# Voltage_regulator.net
KiCad netlist of a schematic drawn in Altium Designer
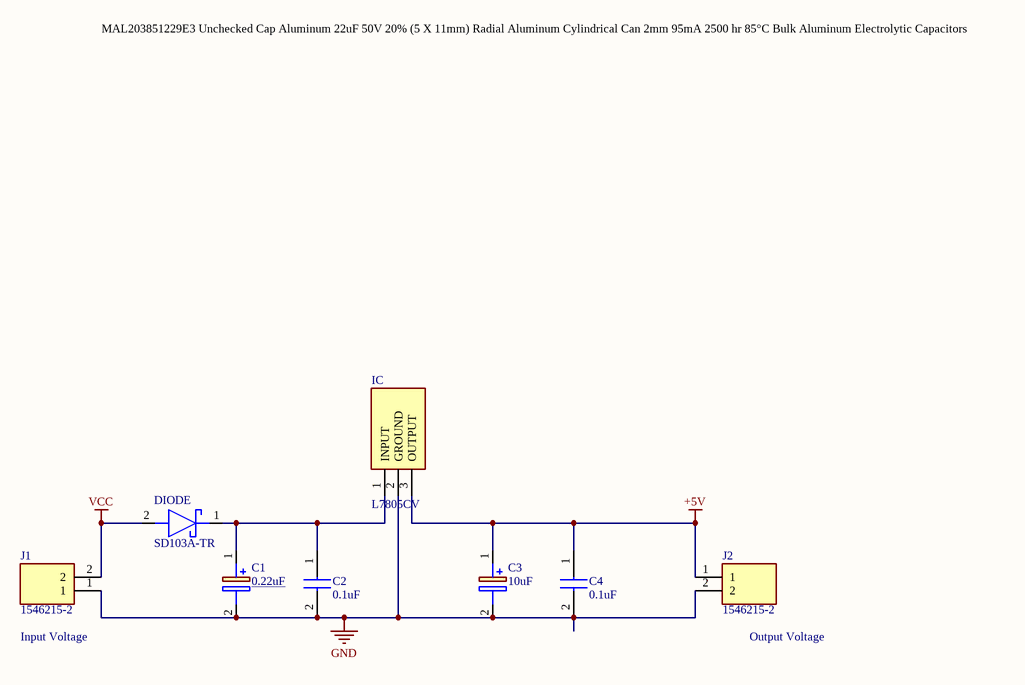
[diagram p0: Voltage_regulator.SchDoc]

(export (version "E")
  (design (tool "Eeschema 10.0.6"))
  (components
    (comp (ref "C1")
      (value "0.22uF")
      (footprint "SamacSys:CAPAE430X600N")
      (description "Capacitor Polarised")
      (fields
        (field (name "MANUFACTURER_PART_NUMBER") "224SML050MD4")
        (field (name "MOUSER PART NUMBER") "598-224SML050MD4")
      )
      (libsource (lib "*") (part "224SML050MD4"))
    )
    (comp (ref "C2")
      (value "0.1uF")
      (footprint "SamacSys:S104Z93Z5VL83L0R")
      (description "Capacitor")
      (fields
        (field (name "MANUFACTURER_PART_NUMBER") "S104Z93Z5VL83L0R")
        (field (name "MOUSER PART NUMBER") "594-S104Z93Z5VL83L0R")
      )
      (libsource (lib "*") (part "S104Z93Z5VL83L0R"))
    )
    (comp (ref "C3")
      (value "10uF")
      (footprint "SamacSys:CAPPRD200W55D500H1250")
      (description "Capacitor Polarised")
      (fields
        (field (name "MANUFACTURER_PART_NUMBER") "EEU-FR1H100")
        (field (name "MOUSER PART NUMBER") "667-EEU-FR1H100")
      )
      (libsource (lib "*") (part "EEU-FR1H100"))
    )
    (comp (ref "C4")
      (value "0.1uF")
      (footprint "SamacSys:S104Z93Z5VL83L0R")
      (description "Capacitor")
      (fields
        (field (name "MANUFACTURER_PART_NUMBER") "S104Z93Z5VL83L0R")
        (field (name "MOUSER PART NUMBER") "594-S104Z93Z5VL83L0R")
      )
      (libsource (lib "*") (part "S104Z93Z5VL83L0R"))
    )
    (comp (ref "DIODE")
      (value "SD103A-TR")
      (footprint "SamacSys:DIOAD950W60L350D150")
      (description "Schottky Diode")
      (fields (field (name "MOUSER PART NUMBER") "625-SD103A"))
      (libsource (lib "*") (part "SD103A-TR"))
    )
    (comp (ref "IC")
      (value "L7805CV")
      (footprint "SamacSys:TO255P460X1020X2008-3P")
      (description "Integrated Circuit")
      (fields (field (name "MOUSER PART NUMBER") "511-L7805CV"))
      (libsource (lib "*") (part "L7805CV"))
    )
    (comp (ref "J1")
      (value "1546215-2")
      (footprint "SamacSys:15462152")
      (description "Connector")
      (fields (field (name "MOUSER PART NUMBER") "571-1546215-2"))
      (libsource (lib "*") (part "1546215-2"))
    )
    (comp (ref "J2")
      (value "1546215-2")
      (footprint "SamacSys:15462152")
      (description "Connector")
      (fields (field (name "MOUSER PART NUMBER") "571-1546215-2"))
      (libsource (lib "") (part "1546215-2_1"))
    )
  )
  (nets
    (net (code "1") (name "+5V") (class "Default")
      (node (ref "C3") (pin "1") (pinfunction "+_1") (pintype "power_in"))
      (node (ref "C4") (pin "1") (pinfunction "1_1") (pintype "passive"))
      (node (ref "IC") (pin "3") (pinfunction "OUTPUT_3") (pintype "passive"))
      (node (ref "J2") (pin "1") (pinfunction "1_1") (pintype "passive"))
    )
    (net (code "2") (name "GND") (class "Default")
      (node (ref "C1") (pin "2") (pinfunction "-_2") (pintype "passive"))
      (node (ref "C2") (pin "2") (pinfunction "2_2") (pintype "passive"))
      (node (ref "C3") (pin "2") (pinfunction "-_2") (pintype "power_in"))
      (node (ref "C4") (pin "2") (pinfunction "2_2") (pintype "passive"))
      (node (ref "IC") (pin "2") (pinfunction "GROUND_2") (pintype "passive"))
      (node (ref "J1") (pin "1") (pinfunction "1_1") (pintype "passive"))
      (node (ref "J2") (pin "2") (pinfunction "2_2") (pintype "passive"))
    )
    (net (code "3") (name "Net-(C1-+)") (class "Default")
      (node (ref "C1") (pin "1") (pinfunction "+_1") (pintype "passive"))
      (node (ref "C2") (pin "1") (pinfunction "1_1") (pintype "passive"))
      (node (ref "DIODE") (pin "1") (pinfunction "K_1") (pintype "passive"))
      (node (ref "IC") (pin "1") (pinfunction "INPUT_1") (pintype "passive"))
    )
    (net (code "4") (name "VCC") (class "Default")
      (node (ref "DIODE") (pin "2") (pinfunction "A_2") (pintype "passive"))
      (node (ref "J1") (pin "2") (pinfunction "2_2") (pintype "passive"))
    )
  )
)
